# board.net
KiCad netlist of a schematic drawn in EAGLE
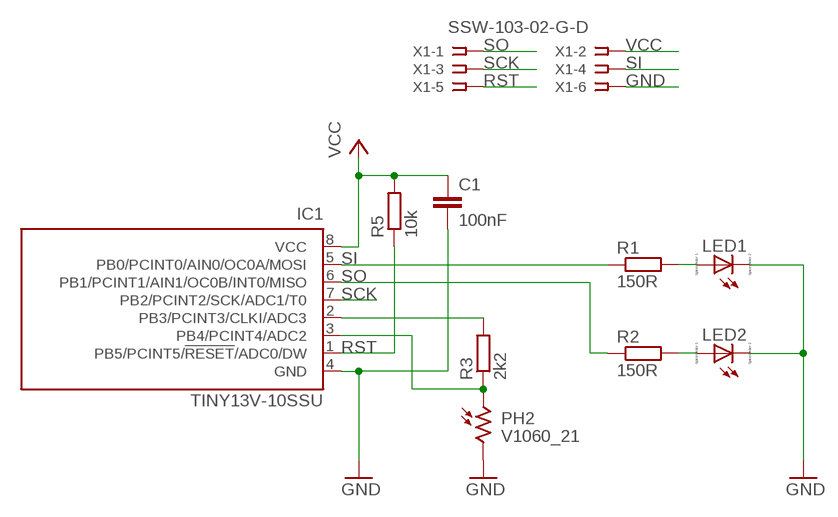
[diagram p0: schematic, sheet 1]

(export (version "E")
  (design (tool "Eeschema 10.0.6"))
  (components
    (comp (ref "C1")
      (value "100nF")
      (footprint "eagle-import:C1206K")
      (libsource (lib "eagle-import") (part "C-EUC1206K"))
    )
    (comp (ref "IC1")
      (value "TINY13V-10SSU")
      (footprint "eagle-import:8S1")
      (fields (field (name "MPN") "ATTINY13V-10SSU"))
      (libsource (lib "eagle-import") (part "TINY13SSUV-10"))
    )
    (comp (ref "LED1")
      (value "LED_ESML0603")
      (footprint "eagle-import:LED_SML0603")
      (libsource (lib "eagle-import") (part "LED_ESML0603"))
    )
    (comp (ref "LED2")
      (value "LED_ESML0603")
      (footprint "eagle-import:LED_SML0603")
      (libsource (lib "eagle-import") (part "LED_ESML0603"))
    )
    (comp (ref "PH2")
      (value "V1060_21")
      (footprint "eagle-import:TO-5_V10")
      (libsource (lib "eagle-import") (part "?1060V_21"))
    )
    (comp (ref "R1")
      (value "150R")
      (footprint "eagle-import:0204_5")
      (libsource (lib "eagle-import") (part "R-EU_0204/5"))
    )
    (comp (ref "R2")
      (value "150R")
      (footprint "eagle-import:0204_5")
      (libsource (lib "eagle-import") (part "R-EU_0204/5"))
    )
    (comp (ref "R3")
      (value "2k2")
      (footprint "eagle-import:0204_5")
      (libsource (lib "eagle-import") (part "R-EU_0204/5"))
    )
    (comp (ref "R5")
      (value "10k")
      (footprint "eagle-import:0204_5")
      (libsource (lib "eagle-import") (part "R-EU_0204/5"))
    )
    (comp (ref "X1")
      (value "SSW-103-02-G-D")
      (footprint "eagle-import:SSW-103-02-G-D")
      (fields (field (name "MF") "Samtec Inc."))
      (libsource (lib "eagle-import") (part "SSW-103-02-G-D"))
    )
  )
  (nets
    (net (code "1") (name "/RST") (class "Default")
      (node (ref "IC1") (pin "1") (pinfunction "PB5/PCINT5/~{RESET}/ADC0/DW_1") (pintype "bidirectional"))
      (node (ref "R5") (pin "1") (pinfunction "1_1") (pintype "passive"))
      (node (ref "X1") (pin "5") (pinfunction "1_5") (pintype "passive"))
    )
    (net (code "2") (name "/SCK") (class "Default")
      (node (ref "IC1") (pin "7") (pinfunction "PB2/PCINT2/SCK/ADC1/T0_7") (pintype "bidirectional"))
      (node (ref "X1") (pin "3") (pinfunction "1_3") (pintype "passive"))
    )
    (net (code "3") (name "/SI") (class "Default")
      (node (ref "IC1") (pin "5") (pinfunction "PB0/PCINT0/AIN0/OC0A/MOSI_5") (pintype "bidirectional"))
      (node (ref "R1") (pin "1") (pinfunction "1_1") (pintype "passive"))
      (node (ref "X1") (pin "4") (pinfunction "1_4") (pintype "passive"))
    )
    (net (code "4") (name "/SO") (class "Default")
      (node (ref "IC1") (pin "6") (pinfunction "PB1/PCINT1/AIN1/OC0B/INT0/MISO_6") (pintype "bidirectional"))
      (node (ref "R2") (pin "1") (pinfunction "1_1") (pintype "passive"))
      (node (ref "X1") (pin "1") (pinfunction "1_1") (pintype "passive"))
    )
    (net (code "5") (name "GND") (class "Default")
      (node (ref "C1") (pin "2") (pinfunction "2_2") (pintype "passive"))
      (node (ref "IC1") (pin "4") (pinfunction "GND_4") (pintype "power_in"))
      (node (ref "LED1") (pin "C") (pinfunction "C_C") (pintype "passive"))
      (node (ref "LED2") (pin "C") (pinfunction "C_C") (pintype "passive"))
      (node (ref "PH2") (pin "2") (pinfunction "2_2") (pintype "passive"))
      (node (ref "X1") (pin "6") (pinfunction "1_6") (pintype "passive"))
    )
    (net (code "6") (name "Net-(IC1-PB3{slash}PCINT3{slash}CLKI{slash}ADC3)") (class "Default")
      (node (ref "IC1") (pin "2") (pinfunction "PB3/PCINT3/CLKI/ADC3_2") (pintype "bidirectional"))
      (node (ref "R3") (pin "2") (pinfunction "2_2") (pintype "passive"))
    )
    (net (code "7") (name "Net-(IC1-PB4{slash}PCINT4{slash}ADC2)") (class "Default")
      (node (ref "IC1") (pin "3") (pinfunction "PB4/PCINT4/ADC2_3") (pintype "bidirectional"))
      (node (ref "PH2") (pin "1") (pinfunction "1_1") (pintype "passive"))
      (node (ref "R3") (pin "1") (pinfunction "1_1") (pintype "passive"))
    )
    (net (code "8") (name "Net-(LED1-PadA)") (class "Default")
      (node (ref "LED1") (pin "A") (pinfunction "A_A") (pintype "passive"))
      (node (ref "R1") (pin "2") (pinfunction "2_2") (pintype "passive"))
    )
    (net (code "9") (name "Net-(LED2-PadA)") (class "Default")
      (node (ref "LED2") (pin "A") (pinfunction "A_A") (pintype "passive"))
      (node (ref "R2") (pin "2") (pinfunction "2_2") (pintype "passive"))
    )
    (net (code "10") (name "VCC") (class "Default")
      (node (ref "C1") (pin "1") (pinfunction "1_1") (pintype "passive"))
      (node (ref "IC1") (pin "8") (pinfunction "VCC_8") (pintype "power_in"))
      (node (ref "R5") (pin "2") (pinfunction "2_2") (pintype "passive"))
      (node (ref "X1") (pin "2") (pinfunction "1_2") (pintype "passive"))
    )
  )
)
